# Shift_Rotate.net
KiCad netlist of a schematic drawn in EAGLE
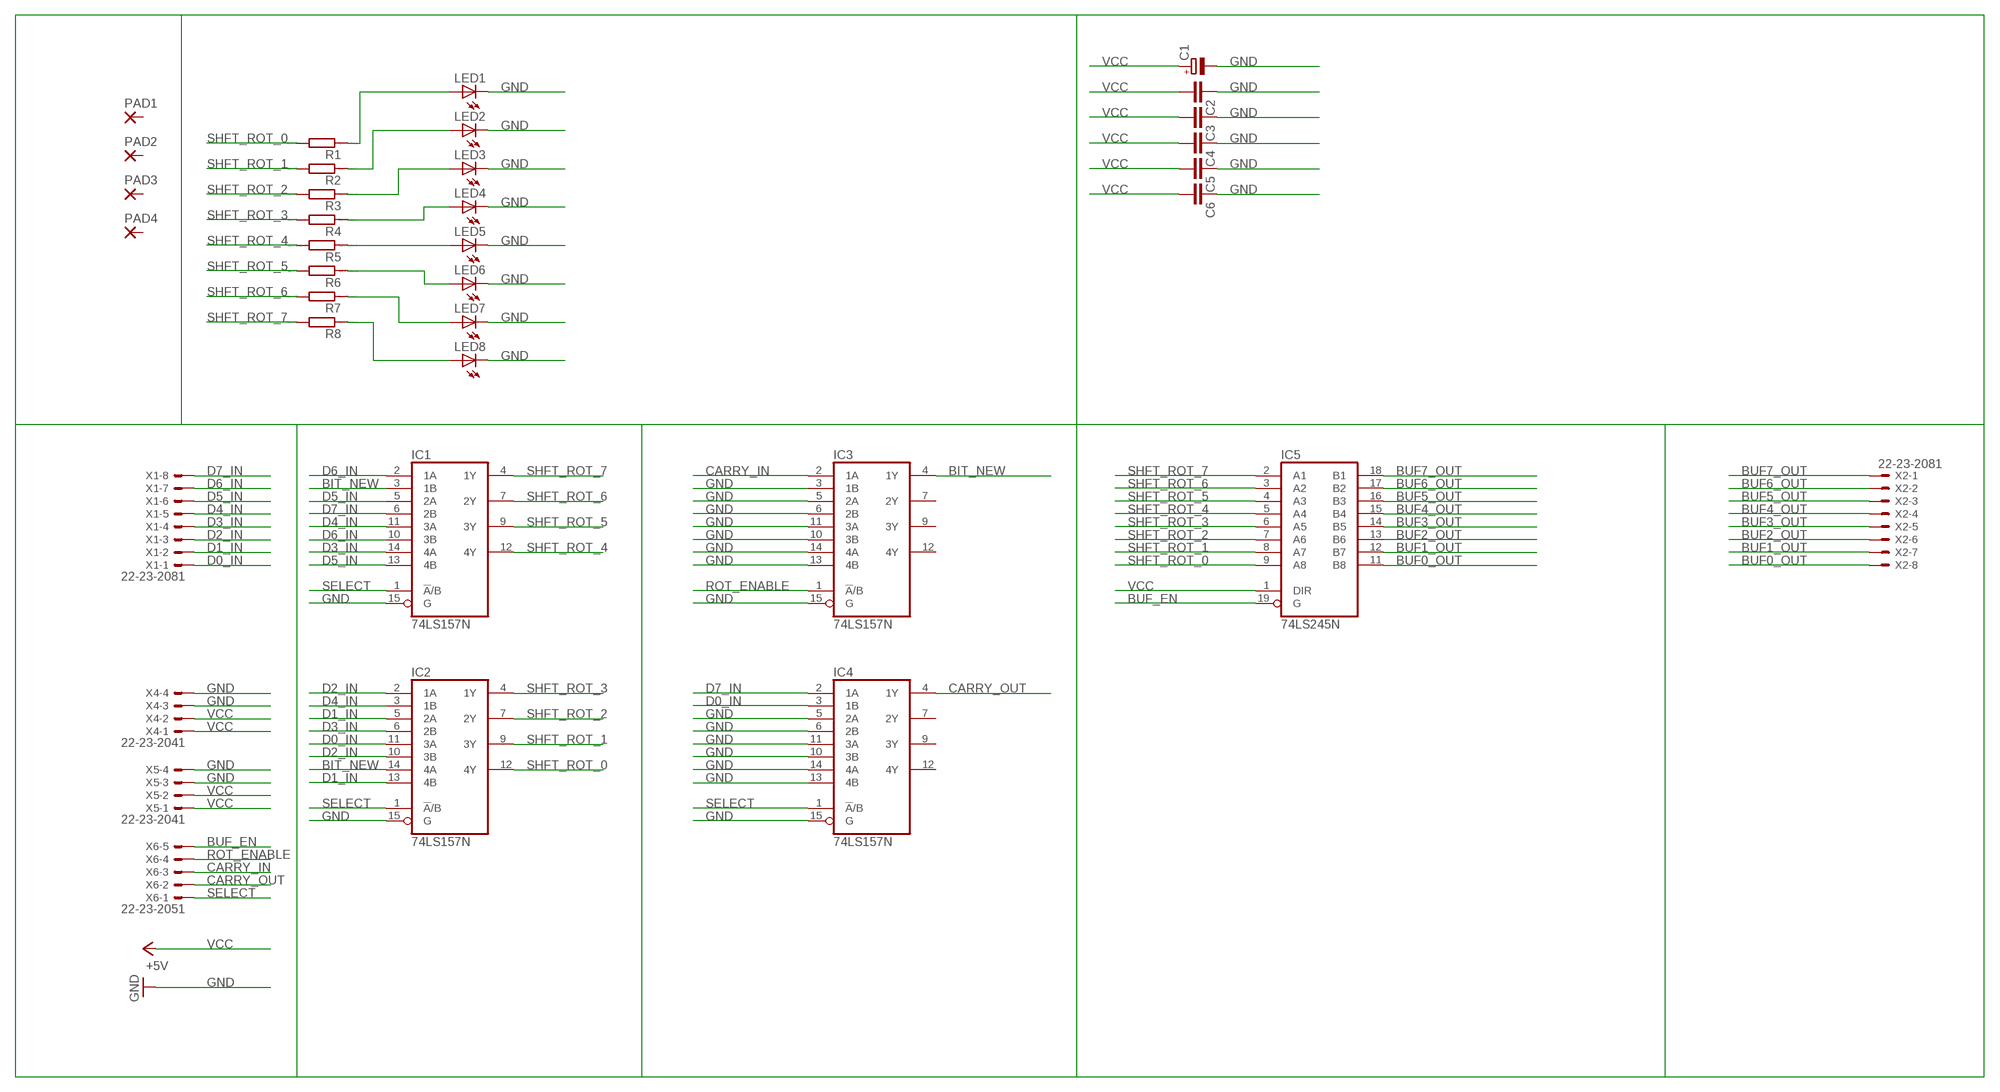
[diagram p0: schematic, sheet 1]

(export (version "E")
  (design (tool "Eeschema 10.0.6"))
  (components
    (comp (ref "C1")
      (value "CPOL-EUE2.5-6")
      (footprint "eagle-import:E2,5-6")
      (libsource (lib "eagle-import") (part "CPOL-EUE2.5-6"))
    )
    (comp (ref "C2")
      (value "C-EU025-025X050")
      (footprint "eagle-import:C025-025X050")
      (libsource (lib "eagle-import") (part "C-EU025-025X050"))
    )
    (comp (ref "C3")
      (value "C-EU025-025X050")
      (footprint "eagle-import:C025-025X050")
      (libsource (lib "eagle-import") (part "C-EU025-025X050"))
    )
    (comp (ref "C4")
      (value "C-EU025-025X050")
      (footprint "eagle-import:C025-025X050")
      (libsource (lib "eagle-import") (part "C-EU025-025X050"))
    )
    (comp (ref "C5")
      (value "C-EU025-025X050")
      (footprint "eagle-import:C025-025X050")
      (libsource (lib "eagle-import") (part "C-EU025-025X050"))
    )
    (comp (ref "C6")
      (value "C-EU025-025X050")
      (footprint "eagle-import:C025-025X050")
      (libsource (lib "eagle-import") (part "C-EU025-025X050"))
    )
    (comp (ref "IC1")
      (value "74LS157N")
      (footprint "eagle-import:DIL16")
      (libsource (lib "eagle-import") (part "74157NLS"))
    )
    (comp (ref "IC2")
      (value "74LS157N")
      (footprint "eagle-import:DIL16")
      (libsource (lib "eagle-import") (part "74157NLS"))
    )
    (comp (ref "IC3")
      (value "74LS157N")
      (footprint "eagle-import:DIL16")
      (libsource (lib "eagle-import") (part "74157NLS"))
    )
    (comp (ref "IC4")
      (value "74LS157N")
      (footprint "eagle-import:DIL16")
      (libsource (lib "eagle-import") (part "74157NLS"))
    )
    (comp (ref "IC5")
      (value "74LS245N")
      (footprint "eagle-import:DIL20")
      (libsource (lib "eagle-import") (part "74245NLS"))
    )
    (comp (ref "LED1")
      (value "LED5MM")
      (footprint "eagle-import:LED5MM")
      (libsource (lib "eagle-import") (part "LED5MM"))
    )
    (comp (ref "LED2")
      (value "LED5MM")
      (footprint "eagle-import:LED5MM")
      (libsource (lib "eagle-import") (part "LED5MM"))
    )
    (comp (ref "LED3")
      (value "LED5MM")
      (footprint "eagle-import:LED5MM")
      (libsource (lib "eagle-import") (part "LED5MM"))
    )
    (comp (ref "LED4")
      (value "LED5MM")
      (footprint "eagle-import:LED5MM")
      (libsource (lib "eagle-import") (part "LED5MM"))
    )
    (comp (ref "LED5")
      (value "LED5MM")
      (footprint "eagle-import:LED5MM")
      (libsource (lib "eagle-import") (part "LED5MM"))
    )
    (comp (ref "LED6")
      (value "LED5MM")
      (footprint "eagle-import:LED5MM")
      (libsource (lib "eagle-import") (part "LED5MM"))
    )
    (comp (ref "LED7")
      (value "LED5MM")
      (footprint "eagle-import:LED5MM")
      (libsource (lib "eagle-import") (part "LED5MM"))
    )
    (comp (ref "LED8")
      (value "LED5MM")
      (footprint "eagle-import:LED5MM")
      (libsource (lib "eagle-import") (part "LED5MM"))
    )
    (comp (ref "PAD1")
      (value "3,17/1,3")
      (footprint "eagle-import:3,17_1,3")
      (libsource (lib "eagle-import") (part "3,17/1,3"))
    )
    (comp (ref "PAD2")
      (value "3,17/1,3")
      (footprint "eagle-import:3,17_1,3")
      (libsource (lib "eagle-import") (part "3,17/1,3"))
    )
    (comp (ref "PAD3")
      (value "3,17/1,3")
      (footprint "eagle-import:3,17_1,3")
      (libsource (lib "eagle-import") (part "3,17/1,3"))
    )
    (comp (ref "PAD4")
      (value "3,17/1,3")
      (footprint "eagle-import:3,17_1,3")
      (libsource (lib "eagle-import") (part "3,17/1,3"))
    )
    (comp (ref "R1")
      (value "R0207/10")
      (footprint "eagle-import:0207_10")
      (libsource (lib "eagle-import") (part "R0207/10"))
    )
    (comp (ref "R2")
      (value "R0207/10")
      (footprint "eagle-import:0207_10")
      (libsource (lib "eagle-import") (part "R0207/10"))
    )
    (comp (ref "R3")
      (value "R0207/10")
      (footprint "eagle-import:0207_10")
      (libsource (lib "eagle-import") (part "R0207/10"))
    )
    (comp (ref "R4")
      (value "R0207/10")
      (footprint "eagle-import:0207_10")
      (libsource (lib "eagle-import") (part "R0207/10"))
    )
    (comp (ref "R5")
      (value "R0207/10")
      (footprint "eagle-import:0207_10")
      (libsource (lib "eagle-import") (part "R0207/10"))
    )
    (comp (ref "R6")
      (value "R0207/10")
      (footprint "eagle-import:0207_10")
      (libsource (lib "eagle-import") (part "R0207/10"))
    )
    (comp (ref "R7")
      (value "R0207/10")
      (footprint "eagle-import:0207_10")
      (libsource (lib "eagle-import") (part "R0207/10"))
    )
    (comp (ref "R8")
      (value "R0207/10")
      (footprint "eagle-import:0207_10")
      (libsource (lib "eagle-import") (part "R0207/10"))
    )
    (comp (ref "X1")
      (value "22-23-2081")
      (footprint "eagle-import:22-23-2081")
      (fields (field (name "MF") "MOLEX"))
      (libsource (lib "eagle-import") (part "22-23-2081"))
    )
    (comp (ref "X2")
      (value "22-23-2081")
      (footprint "eagle-import:22-23-2081")
      (fields (field (name "MF") "MOLEX"))
      (libsource (lib "eagle-import") (part "22-23-2081"))
    )
    (comp (ref "X4")
      (value "22-23-2041")
      (footprint "eagle-import:22-23-2041")
      (fields (field (name "MF") "MOLEX"))
      (libsource (lib "eagle-import") (part "22-23-2041"))
    )
    (comp (ref "X5")
      (value "22-23-2041")
      (footprint "eagle-import:22-23-2041")
      (fields (field (name "MF") "MOLEX"))
      (libsource (lib "eagle-import") (part "22-23-2041"))
    )
    (comp (ref "X6")
      (value "22-23-2051")
      (footprint "eagle-import:22-23-2051")
      (fields (field (name "MF") "MOLEX"))
      (libsource (lib "eagle-import") (part "22-23-2051"))
    )
  )
  (nets
    (net (code "1") (name "+5V") (class "Default")
      (node (ref "C1") (pin "+") (pinfunction "+_+") (pintype "passive"))
      (node (ref "C2") (pin "2") (pinfunction "2_2") (pintype "passive"))
      (node (ref "C3") (pin "2") (pinfunction "2_2") (pintype "passive"))
      (node (ref "C4") (pin "2") (pinfunction "2_2") (pintype "passive"))
      (node (ref "C5") (pin "2") (pinfunction "2_2") (pintype "passive"))
      (node (ref "C6") (pin "2") (pinfunction "2_2") (pintype "passive"))
      (node (ref "IC5") (pin "1") (pinfunction "DIR_1") (pintype "input"))
      (node (ref "X4") (pin "1") (pinfunction "S_1") (pintype "passive"))
      (node (ref "X4") (pin "2") (pinfunction "S_2") (pintype "passive"))
      (node (ref "X5") (pin "1") (pinfunction "S_1") (pintype "passive"))
      (node (ref "X5") (pin "2") (pinfunction "S_2") (pintype "passive"))
    )
    (net (code "2") (name "/BIT_NEW") (class "Default")
      (node (ref "IC1") (pin "3") (pinfunction "1B_3") (pintype "input"))
      (node (ref "IC2") (pin "14") (pinfunction "4A_14") (pintype "input"))
      (node (ref "IC3") (pin "4") (pinfunction "1Y_4") (pintype "output"))
    )
    (net (code "3") (name "/BUF0_OUT") (class "Default")
      (node (ref "IC5") (pin "11") (pinfunction "B8_11") (pintype "bidirectional"))
      (node (ref "X2") (pin "8") (pinfunction "S_8") (pintype "passive"))
    )
    (net (code "4") (name "/BUF1_OUT") (class "Default")
      (node (ref "IC5") (pin "12") (pinfunction "B7_12") (pintype "bidirectional"))
      (node (ref "X2") (pin "7") (pinfunction "S_7") (pintype "passive"))
    )
    (net (code "5") (name "/BUF2_OUT") (class "Default")
      (node (ref "IC5") (pin "13") (pinfunction "B6_13") (pintype "bidirectional"))
      (node (ref "X2") (pin "6") (pinfunction "S_6") (pintype "passive"))
    )
    (net (code "6") (name "/BUF3_OUT") (class "Default")
      (node (ref "IC5") (pin "14") (pinfunction "B5_14") (pintype "bidirectional"))
      (node (ref "X2") (pin "5") (pinfunction "S_5") (pintype "passive"))
    )
    (net (code "7") (name "/BUF4_OUT") (class "Default")
      (node (ref "IC5") (pin "15") (pinfunction "B4_15") (pintype "bidirectional"))
      (node (ref "X2") (pin "4") (pinfunction "S_4") (pintype "passive"))
    )
    (net (code "8") (name "/BUF5_OUT") (class "Default")
      (node (ref "IC5") (pin "16") (pinfunction "B3_16") (pintype "bidirectional"))
      (node (ref "X2") (pin "3") (pinfunction "S_3") (pintype "passive"))
    )
    (net (code "9") (name "/BUF6_OUT") (class "Default")
      (node (ref "IC5") (pin "17") (pinfunction "B2_17") (pintype "bidirectional"))
      (node (ref "X2") (pin "2") (pinfunction "S_2") (pintype "passive"))
    )
    (net (code "10") (name "/BUF7_OUT") (class "Default")
      (node (ref "IC5") (pin "18") (pinfunction "B1_18") (pintype "bidirectional"))
      (node (ref "X2") (pin "1") (pinfunction "S_1") (pintype "passive"))
    )
    (net (code "11") (name "/BUF_EN") (class "Default")
      (node (ref "IC5") (pin "19") (pinfunction "G_19") (pintype "input"))
      (node (ref "X6") (pin "5") (pinfunction "S_5") (pintype "passive"))
    )
    (net (code "12") (name "/CARRY_IN") (class "Default")
      (node (ref "IC3") (pin "2") (pinfunction "1A_2") (pintype "input"))
      (node (ref "X6") (pin "3") (pinfunction "S_3") (pintype "passive"))
    )
    (net (code "13") (name "/CARRY_OUT") (class "Default")
      (node (ref "IC4") (pin "4") (pinfunction "1Y_4") (pintype "output"))
      (node (ref "X6") (pin "2") (pinfunction "S_2") (pintype "passive"))
    )
    (net (code "14") (name "/D0_IN") (class "Default")
      (node (ref "IC2") (pin "11") (pinfunction "3A_11") (pintype "input"))
      (node (ref "IC4") (pin "3") (pinfunction "1B_3") (pintype "input"))
      (node (ref "X1") (pin "1") (pinfunction "S_1") (pintype "passive"))
    )
    (net (code "15") (name "/D1_IN") (class "Default")
      (node (ref "IC2") (pin "13") (pinfunction "4B_13") (pintype "input"))
      (node (ref "IC2") (pin "5") (pinfunction "2A_5") (pintype "input"))
      (node (ref "X1") (pin "2") (pinfunction "S_2") (pintype "passive"))
    )
    (net (code "16") (name "/D2_IN") (class "Default")
      (node (ref "IC2") (pin "10") (pinfunction "3B_10") (pintype "input"))
      (node (ref "IC2") (pin "2") (pinfunction "1A_2") (pintype "input"))
      (node (ref "X1") (pin "3") (pinfunction "S_3") (pintype "passive"))
    )
    (net (code "17") (name "/D3_IN") (class "Default")
      (node (ref "IC1") (pin "14") (pinfunction "4A_14") (pintype "input"))
      (node (ref "IC2") (pin "6") (pinfunction "2B_6") (pintype "input"))
      (node (ref "X1") (pin "4") (pinfunction "S_4") (pintype "passive"))
    )
    (net (code "18") (name "/D4_IN") (class "Default")
      (node (ref "IC1") (pin "11") (pinfunction "3A_11") (pintype "input"))
      (node (ref "IC2") (pin "3") (pinfunction "1B_3") (pintype "input"))
      (node (ref "X1") (pin "5") (pinfunction "S_5") (pintype "passive"))
    )
    (net (code "19") (name "/D5_IN") (class "Default")
      (node (ref "IC1") (pin "13") (pinfunction "4B_13") (pintype "input"))
      (node (ref "IC1") (pin "5") (pinfunction "2A_5") (pintype "input"))
      (node (ref "X1") (pin "6") (pinfunction "S_6") (pintype "passive"))
    )
    (net (code "20") (name "/D6_IN") (class "Default")
      (node (ref "IC1") (pin "10") (pinfunction "3B_10") (pintype "input"))
      (node (ref "IC1") (pin "2") (pinfunction "1A_2") (pintype "input"))
      (node (ref "X1") (pin "7") (pinfunction "S_7") (pintype "passive"))
    )
    (net (code "21") (name "/D7_IN") (class "Default")
      (node (ref "IC1") (pin "6") (pinfunction "2B_6") (pintype "input"))
      (node (ref "IC4") (pin "2") (pinfunction "1A_2") (pintype "input"))
      (node (ref "X1") (pin "8") (pinfunction "S_8") (pintype "passive"))
    )
    (net (code "22") (name "/ROT_ENABLE") (class "Default")
      (node (ref "IC3") (pin "1") (pinfunction "~{A}/B_1") (pintype "input"))
      (node (ref "X6") (pin "4") (pinfunction "S_4") (pintype "passive"))
    )
    (net (code "23") (name "/SELECT") (class "Default")
      (node (ref "IC1") (pin "1") (pinfunction "~{A}/B_1") (pintype "input"))
      (node (ref "IC2") (pin "1") (pinfunction "~{A}/B_1") (pintype "input"))
      (node (ref "IC4") (pin "1") (pinfunction "~{A}/B_1") (pintype "input"))
      (node (ref "X6") (pin "1") (pinfunction "S_1") (pintype "passive"))
    )
    (net (code "24") (name "/SHFT_ROT_0") (class "Default")
      (node (ref "IC2") (pin "12") (pinfunction "4Y_12") (pintype "output"))
      (node (ref "IC5") (pin "9") (pinfunction "A8_9") (pintype "bidirectional"))
      (node (ref "R1") (pin "2") (pinfunction "2_2") (pintype "passive"))
    )
    (net (code "25") (name "/SHFT_ROT_1") (class "Default")
      (node (ref "IC2") (pin "9") (pinfunction "3Y_9") (pintype "output"))
      (node (ref "IC5") (pin "8") (pinfunction "A7_8") (pintype "bidirectional"))
      (node (ref "R2") (pin "2") (pinfunction "2_2") (pintype "passive"))
    )
    (net (code "26") (name "/SHFT_ROT_2") (class "Default")
      (node (ref "IC2") (pin "7") (pinfunction "2Y_7") (pintype "output"))
      (node (ref "IC5") (pin "7") (pinfunction "A6_7") (pintype "bidirectional"))
      (node (ref "R3") (pin "2") (pinfunction "2_2") (pintype "passive"))
    )
    (net (code "27") (name "/SHFT_ROT_3") (class "Default")
      (node (ref "IC2") (pin "4") (pinfunction "1Y_4") (pintype "output"))
      (node (ref "IC5") (pin "6") (pinfunction "A5_6") (pintype "bidirectional"))
      (node (ref "R4") (pin "2") (pinfunction "2_2") (pintype "passive"))
    )
    (net (code "28") (name "/SHFT_ROT_4") (class "Default")
      (node (ref "IC1") (pin "12") (pinfunction "4Y_12") (pintype "output"))
      (node (ref "IC5") (pin "5") (pinfunction "A4_5") (pintype "bidirectional"))
      (node (ref "R5") (pin "2") (pinfunction "2_2") (pintype "passive"))
    )
    (net (code "29") (name "/SHFT_ROT_5") (class "Default")
      (node (ref "IC1") (pin "9") (pinfunction "3Y_9") (pintype "output"))
      (node (ref "IC5") (pin "4") (pinfunction "A3_4") (pintype "bidirectional"))
      (node (ref "R6") (pin "2") (pinfunction "2_2") (pintype "passive"))
    )
    (net (code "30") (name "/SHFT_ROT_6") (class "Default")
      (node (ref "IC1") (pin "7") (pinfunction "2Y_7") (pintype "output"))
      (node (ref "IC5") (pin "3") (pinfunction "A2_3") (pintype "bidirectional"))
      (node (ref "R7") (pin "2") (pinfunction "2_2") (pintype "passive"))
    )
    (net (code "31") (name "/SHFT_ROT_7") (class "Default")
      (node (ref "IC1") (pin "4") (pinfunction "1Y_4") (pintype "output"))
      (node (ref "IC5") (pin "2") (pinfunction "A1_2") (pintype "bidirectional"))
      (node (ref "R8") (pin "2") (pinfunction "2_2") (pintype "passive"))
    )
    (net (code "32") (name "GND") (class "Default")
      (node (ref "C1") (pin "-") (pinfunction "-_-") (pintype "passive"))
      (node (ref "C2") (pin "1") (pinfunction "1_1") (pintype "passive"))
      (node (ref "C3") (pin "1") (pinfunction "1_1") (pintype "passive"))
      (node (ref "C4") (pin "1") (pinfunction "1_1") (pintype "passive"))
      (node (ref "C5") (pin "1") (pinfunction "1_1") (pintype "passive"))
      (node (ref "C6") (pin "1") (pinfunction "1_1") (pintype "passive"))
      (node (ref "IC1") (pin "15") (pinfunction "G_15") (pintype "input"))
      (node (ref "IC2") (pin "15") (pinfunction "G_15") (pintype "input"))
      (node (ref "IC3") (pin "10") (pinfunction "3B_10") (pintype "input"))
      (node (ref "IC3") (pin "11") (pinfunction "3A_11") (pintype "input"))
      (node (ref "IC3") (pin "13") (pinfunction "4B_13") (pintype "input"))
      (node (ref "IC3") (pin "14") (pinfunction "4A_14") (pintype "input"))
      (node (ref "IC3") (pin "15") (pinfunction "G_15") (pintype "input"))
      (node (ref "IC3") (pin "3") (pinfunction "1B_3") (pintype "input"))
      (node (ref "IC3") (pin "5") (pinfunction "2A_5") (pintype "input"))
      (node (ref "IC3") (pin "6") (pinfunction "2B_6") (pintype "input"))
      (node (ref "IC4") (pin "10") (pinfunction "3B_10") (pintype "input"))
      (node (ref "IC4") (pin "11") (pinfunction "3A_11") (pintype "input"))
      (node (ref "IC4") (pin "13") (pinfunction "4B_13") (pintype "input"))
      (node (ref "IC4") (pin "14") (pinfunction "4A_14") (pintype "input"))
      (node (ref "IC4") (pin "15") (pinfunction "G_15") (pintype "input"))
      (node (ref "IC4") (pin "5") (pinfunction "2A_5") (pintype "input"))
      (node (ref "IC4") (pin "6") (pinfunction "2B_6") (pintype "input"))
      (node (ref "LED1") (pin "K") (pinfunction "C_K") (pintype "passive"))
      (node (ref "LED2") (pin "K") (pinfunction "C_K") (pintype "passive"))
      (node (ref "LED3") (pin "K") (pinfunction "C_K") (pintype "passive"))
      (node (ref "LED4") (pin "K") (pinfunction "C_K") (pintype "passive"))
      (node (ref "LED5") (pin "K") (pinfunction "C_K") (pintype "passive"))
      (node (ref "LED6") (pin "K") (pinfunction "C_K") (pintype "passive"))
      (node (ref "LED7") (pin "K") (pinfunction "C_K") (pintype "passive"))
      (node (ref "LED8") (pin "K") (pinfunction "C_K") (pintype "passive"))
      (node (ref "X4") (pin "3") (pinfunction "S_3") (pintype "passive"))
      (node (ref "X4") (pin "4") (pinfunction "S_4") (pintype "passive"))
      (node (ref "X5") (pin "3") (pinfunction "S_3") (pintype "passive"))
      (node (ref "X5") (pin "4") (pinfunction "S_4") (pintype "passive"))
    )
    (net (code "33") (name "Net-(LED1-PadA)") (class "Default")
      (node (ref "LED1") (pin "A") (pinfunction "A_A") (pintype "passive"))
      (node (ref "R1") (pin "1") (pinfunction "1_1") (pintype "passive"))
    )
    (net (code "34") (name "Net-(LED2-PadA)") (class "Default")
      (node (ref "LED2") (pin "A") (pinfunction "A_A") (pintype "passive"))
      (node (ref "R2") (pin "1") (pinfunction "1_1") (pintype "passive"))
    )
    (net (code "35") (name "Net-(LED3-PadA)") (class "Default")
      (node (ref "LED3") (pin "A") (pinfunction "A_A") (pintype "passive"))
      (node (ref "R3") (pin "1") (pinfunction "1_1") (pintype "passive"))
    )
    (net (code "36") (name "Net-(LED4-PadA)") (class "Default")
      (node (ref "LED4") (pin "A") (pinfunction "A_A") (pintype "passive"))
      (node (ref "R4") (pin "1") (pinfunction "1_1") (pintype "passive"))
    )
    (net (code "37") (name "Net-(LED5-PadA)") (class "Default")
      (node (ref "LED5") (pin "A") (pinfunction "A_A") (pintype "passive"))
      (node (ref "R5") (pin "1") (pinfunction "1_1") (pintype "passive"))
    )
    (net (code "38") (name "Net-(LED6-PadA)") (class "Default")
      (node (ref "LED6") (pin "A") (pinfunction "A_A") (pintype "passive"))
      (node (ref "R6") (pin "1") (pinfunction "1_1") (pintype "passive"))
    )
    (net (code "39") (name "Net-(LED7-PadA)") (class "Default")
      (node (ref "LED7") (pin "A") (pinfunction "A_A") (pintype "passive"))
      (node (ref "R7") (pin "1") (pinfunction "1_1") (pintype "passive"))
    )
    (net (code "40") (name "Net-(LED8-PadA)") (class "Default")
      (node (ref "LED8") (pin "A") (pinfunction "A_A") (pintype "passive"))
      (node (ref "R8") (pin "1") (pinfunction "1_1") (pintype "passive"))
    )
    (net (code "41") (name "unconnected-(IC3A-2Y-Pad7)") (class "Default")
      (node (ref "IC3") (pin "7") (pinfunction "2Y_7") (pintype "output"))
    )
    (net (code "42") (name "unconnected-(IC3A-3Y-Pad9)") (class "Default")
      (node (ref "IC3") (pin "9") (pinfunction "3Y_9") (pintype "output"))
    )
    (net (code "43") (name "unconnected-(IC3A-4Y-Pad12)") (class "Default")
      (node (ref "IC3") (pin "12") (pinfunction "4Y_12") (pintype "output"))
    )
    (net (code "44") (name "unconnected-(IC4A-2Y-Pad7)") (class "Default")
      (node (ref "IC4") (pin "7") (pinfunction "2Y_7") (pintype "output"))
    )
    (net (code "45") (name "unconnected-(IC4A-3Y-Pad9)") (class "Default")
      (node (ref "IC4") (pin "9") (pinfunction "3Y_9") (pintype "output"))
    )
    (net (code "46") (name "unconnected-(IC4A-4Y-Pad12)") (class "Default")
      (node (ref "IC4") (pin "12") (pinfunction "4Y_12") (pintype "output"))
    )
    (net (code "47") (name "unconnected-(PAD1-P-Pad1)") (class "Default")
      (node (ref "PAD1") (pin "1") (pinfunction "P_1") (pintype "passive"))
    )
    (net (code "48") (name "unconnected-(PAD2-P-Pad1)") (class "Default")
      (node (ref "PAD2") (pin "1") (pinfunction "P_1") (pintype "passive"))
    )
    (net (code "49") (name "unconnected-(PAD3-P-Pad1)") (class "Default")
      (node (ref "PAD3") (pin "1") (pinfunction "P_1") (pintype "passive"))
    )
    (net (code "50") (name "unconnected-(PAD4-P-Pad1)") (class "Default")
      (node (ref "PAD4") (pin "1") (pinfunction "P_1") (pintype "passive"))
    )
  )
)
